# Battery_level_meter.net
KiCad netlist of a schematic drawn in Altium Designer
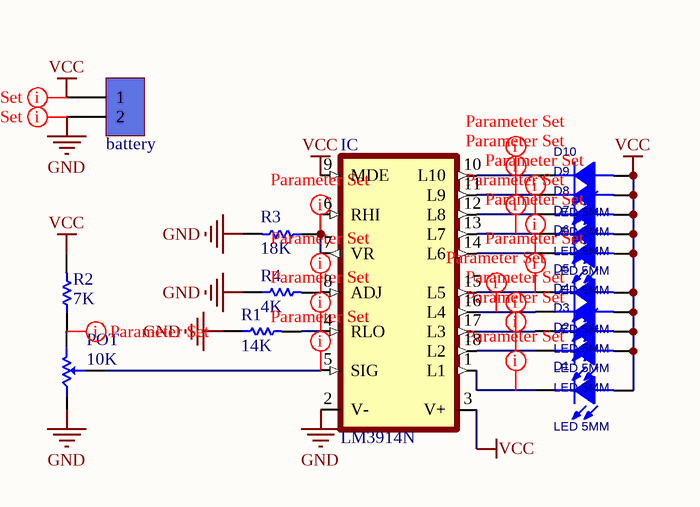
[diagram p0: Battery level meter.SchDoc]

(export (version "E")
  (design (tool "Eeschema 10.0.6"))
  (components
    (comp (ref "battery")
      (value "KF301_Terminal")
      (footprint "KF301 2PIN")
      (description "Terminal 2 Pin 250VAC 16A")
      (fields (field (name "DESIGNER") "Abbas Basereh"))
      (libsource (lib "Altium") (part "KF301-2Pin_Terminal"))
    )
    (comp (ref "D1")
      (value "LED 5MM")
      (footprint "LED5MM_RED")
      (description "Light Emitting Diode")
      (fields (field (name "DESIGNER") "Abbas Basereh"))
      (libsource (lib "Altium") (part "LED 5MM"))
    )
    (comp (ref "D2")
      (value "LED 5MM")
      (footprint "LED5MM_RED")
      (description "Light Emitting Diode")
      (fields (field (name "DESIGNER") "Abbas Basereh"))
      (libsource (lib "Altium") (part "LED 5MM"))
    )
    (comp (ref "D3")
      (value "LED 5MM")
      (footprint "LED5MM_RED")
      (description "Light Emitting Diode")
      (fields (field (name "DESIGNER") "Abbas Basereh"))
      (libsource (lib "Altium") (part "LED 5MM"))
    )
    (comp (ref "D4")
      (value "LED 5MM")
      (footprint "LED5MM_RED")
      (description "Light Emitting Diode")
      (fields (field (name "DESIGNER") "Abbas Basereh"))
      (libsource (lib "Altium") (part "LED 5MM"))
    )
    (comp (ref "D5")
      (value "LED 5MM")
      (footprint "LED5MM_YELLOW")
      (description "Light Emitting Diode")
      (fields (field (name "DESIGNER") "Abbas Basereh"))
      (libsource (lib "Altium") (part "LED 5MM"))
    )
    (comp (ref "D6")
      (value "LED 5MM")
      (footprint "LED5MM_YELLOW")
      (description "Light Emitting Diode")
      (fields (field (name "DESIGNER") "Abbas Basereh"))
      (libsource (lib "Altium") (part "LED 5MM"))
    )
    (comp (ref "D7")
      (value "LED 5MM")
      (footprint "LED5MM_YELLOW")
      (description "Light Emitting Diode")
      (fields (field (name "DESIGNER") "Abbas Basereh"))
      (libsource (lib "Altium") (part "LED 5MM"))
    )
    (comp (ref "D8")
      (value "LED 5MM")
      (footprint "LED5MM_YELLOW")
      (description "Light Emitting Diode")
      (fields (field (name "DESIGNER") "Abbas Basereh"))
      (libsource (lib "Altium") (part "LED 5MM"))
    )
    (comp (ref "D9")
      (value "LED 5MM")
      (footprint "LED5MM_GRN")
      (description "Light Emitting Diode")
      (fields (field (name "DESIGNER") "Abbas Basereh"))
      (libsource (lib "Altium") (part "LED 5MM"))
    )
    (comp (ref "D10")
      (value "LED 5MM")
      (footprint "LED5MM_GRN")
      (description "Light Emitting Diode")
      (fields (field (name "DESIGNER") "Abbas Basereh"))
      (libsource (lib "Altium") (part "LED 5MM"))
    )
    (comp (ref "IC")
      (value "LM3914N")
      (footprint "DIL18")
      (description "LED Lighting Drivers")
      (fields (field (name "MF") "Texas Instruments"))
      (libsource (lib "LM3914N") (part "LM3914N"))
    )
    (comp (ref "POT")
      (value "10K")
      (footprint "POT 4")
      (description "Variable Resistor")
      (libsource (lib "Altium") (part "POT"))
    )
    (comp (ref "R1")
      (value "14K")
      (footprint "RES-(1/1)")
      (description "TOTAL DIP RESISTOR PACK")
      (fields (field (name "DESIGNER") "Ali Hafizi"))
      (libsource (lib "Altium") (part "RES DIP PACKAGE"))
    )
    (comp (ref "R2")
      (value "7K")
      (footprint "RES-(1/1)")
      (description "TOTAL DIP RESISTOR PACK")
      (fields (field (name "DESIGNER") "Ali Hafizi"))
      (libsource (lib "Altium") (part "RES DIP PACKAGE"))
    )
    (comp (ref "R3")
      (value "18K")
      (footprint "RES-(1/1)")
      (description "TOTAL DIP RESISTOR PACK")
      (fields (field (name "DESIGNER") "Ali Hafizi"))
      (libsource (lib "Altium") (part "RES DIP PACKAGE"))
    )
    (comp (ref "R4")
      (value "4K")
      (footprint "RES-(1/1)")
      (description "TOTAL DIP RESISTOR PACK")
      (fields (field (name "DESIGNER") "Ali Hafizi"))
      (libsource (lib "Altium") (part "RES DIP PACKAGE"))
    )
  )
  (nets
    (net (code "1") (name "GND") (class "Default")
      (node (ref "IC") (pin "2") (pinfunction "V-_2") (pintype "power_in"))
      (node (ref "POT") (pin "1") (pinfunction "CCW_1") (pintype "passive"))
      (node (ref "R1") (pin "1") (pinfunction "1_1") (pintype "passive"))
      (node (ref "R3") (pin "2") (pinfunction "2_2") (pintype "passive"))
      (node (ref "R4") (pin "1") (pinfunction "1_1") (pintype "passive"))
      (node (ref "battery") (pin "2") (pinfunction "2_2") (pintype "passive"))
    )
    (net (code "2") (name "Net-(D1-CATHODE)") (class "Default")
      (node (ref "D1") (pin "2") (pinfunction "CATHODE_2") (pintype "passive"))
      (node (ref "IC") (pin "1") (pinfunction "L1_1") (pintype "output"))
    )
    (net (code "3") (name "Net-(D2-CATHODE)") (class "Default")
      (node (ref "D2") (pin "2") (pinfunction "CATHODE_2") (pintype "passive"))
      (node (ref "IC") (pin "18") (pinfunction "L2_18") (pintype "output"))
    )
    (net (code "4") (name "Net-(D3-CATHODE)") (class "Default")
      (node (ref "D3") (pin "2") (pinfunction "CATHODE_2") (pintype "passive"))
      (node (ref "IC") (pin "17") (pinfunction "L3_17") (pintype "output"))
    )
    (net (code "5") (name "Net-(D4-CATHODE)") (class "Default")
      (node (ref "D4") (pin "2") (pinfunction "CATHODE_2") (pintype "passive"))
      (node (ref "IC") (pin "16") (pinfunction "L4_16") (pintype "output"))
    )
    (net (code "6") (name "Net-(D5-CATHODE)") (class "Default")
      (node (ref "D5") (pin "2") (pinfunction "CATHODE_2") (pintype "passive"))
      (node (ref "IC") (pin "15") (pinfunction "L5_15") (pintype "output"))
    )
    (net (code "7") (name "Net-(D6-CATHODE)") (class "Default")
      (node (ref "D6") (pin "2") (pinfunction "CATHODE_2") (pintype "passive"))
      (node (ref "IC") (pin "14") (pinfunction "L6_14") (pintype "output"))
    )
    (net (code "8") (name "Net-(D7-CATHODE)") (class "Default")
      (node (ref "D7") (pin "2") (pinfunction "CATHODE_2") (pintype "passive"))
      (node (ref "IC") (pin "13") (pinfunction "L7_13") (pintype "output"))
    )
    (net (code "9") (name "Net-(D8-CATHODE)") (class "Default")
      (node (ref "D8") (pin "2") (pinfunction "CATHODE_2") (pintype "passive"))
      (node (ref "IC") (pin "12") (pinfunction "L8_12") (pintype "output"))
    )
    (net (code "10") (name "Net-(D9-CATHODE)") (class "Default")
      (node (ref "D9") (pin "2") (pinfunction "CATHODE_2") (pintype "passive"))
      (node (ref "IC") (pin "11") (pinfunction "L9_11") (pintype "output"))
    )
    (net (code "11") (name "Net-(D10-CATHODE)") (class "Default")
      (node (ref "D10") (pin "2") (pinfunction "CATHODE_2") (pintype "passive"))
      (node (ref "IC") (pin "10") (pinfunction "L10_10") (pintype "output"))
    )
    (net (code "12") (name "Net-(IC-ADJ)") (class "Default")
      (node (ref "IC") (pin "8") (pinfunction "ADJ_8") (pintype "input"))
      (node (ref "R4") (pin "2") (pinfunction "2_2") (pintype "passive"))
    )
    (net (code "13") (name "Net-(IC-RHI)") (class "Default")
      (node (ref "IC") (pin "6") (pinfunction "RHI_6") (pintype "input"))
      (node (ref "IC") (pin "7") (pinfunction "VR_7") (pintype "output"))
      (node (ref "R3") (pin "1") (pinfunction "1_1") (pintype "passive"))
    )
    (net (code "14") (name "Net-(IC-RLO)") (class "Default")
      (node (ref "IC") (pin "4") (pinfunction "RLO_4") (pintype "input"))
      (node (ref "R1") (pin "2") (pinfunction "2_2") (pintype "passive"))
    )
    (net (code "15") (name "Net-(IC-SIG)") (class "Default")
      (node (ref "IC") (pin "5") (pinfunction "SIG_5") (pintype "input"))
      (node (ref "POT") (pin "3") (pinfunction "SetPoint_3") (pintype "passive"))
    )
    (net (code "16") (name "Net-(POT-CW)") (class "Default")
      (node (ref "POT") (pin "2") (pinfunction "CW_2") (pintype "passive"))
      (node (ref "R2") (pin "1") (pinfunction "1_1") (pintype "passive"))
    )
    (net (code "17") (name "VCC") (class "Default")
      (node (ref "D1") (pin "1") (pinfunction "ANODE_1") (pintype "passive"))
      (node (ref "D10") (pin "1") (pinfunction "ANODE_1") (pintype "passive"))
      (node (ref "D2") (pin "1") (pinfunction "ANODE_1") (pintype "passive"))
      (node (ref "D3") (pin "1") (pinfunction "ANODE_1") (pintype "passive"))
      (node (ref "D4") (pin "1") (pinfunction "ANODE_1") (pintype "passive"))
      (node (ref "D5") (pin "1") (pinfunction "ANODE_1") (pintype "passive"))
      (node (ref "D6") (pin "1") (pinfunction "ANODE_1") (pintype "passive"))
      (node (ref "D7") (pin "1") (pinfunction "ANODE_1") (pintype "passive"))
      (node (ref "D8") (pin "1") (pinfunction "ANODE_1") (pintype "passive"))
      (node (ref "D9") (pin "1") (pinfunction "ANODE_1") (pintype "passive"))
      (node (ref "IC") (pin "3") (pinfunction "V+_3") (pintype "power_in"))
      (node (ref "IC") (pin "9") (pinfunction "MDE_9") (pintype "input"))
      (node (ref "R2") (pin "2") (pinfunction "2_2") (pintype "passive"))
      (node (ref "battery") (pin "1") (pinfunction "1_1") (pintype "passive"))
    )
  )
)
